# 2.net
KiCad netlist of a schematic drawn in EasyEDA Pro
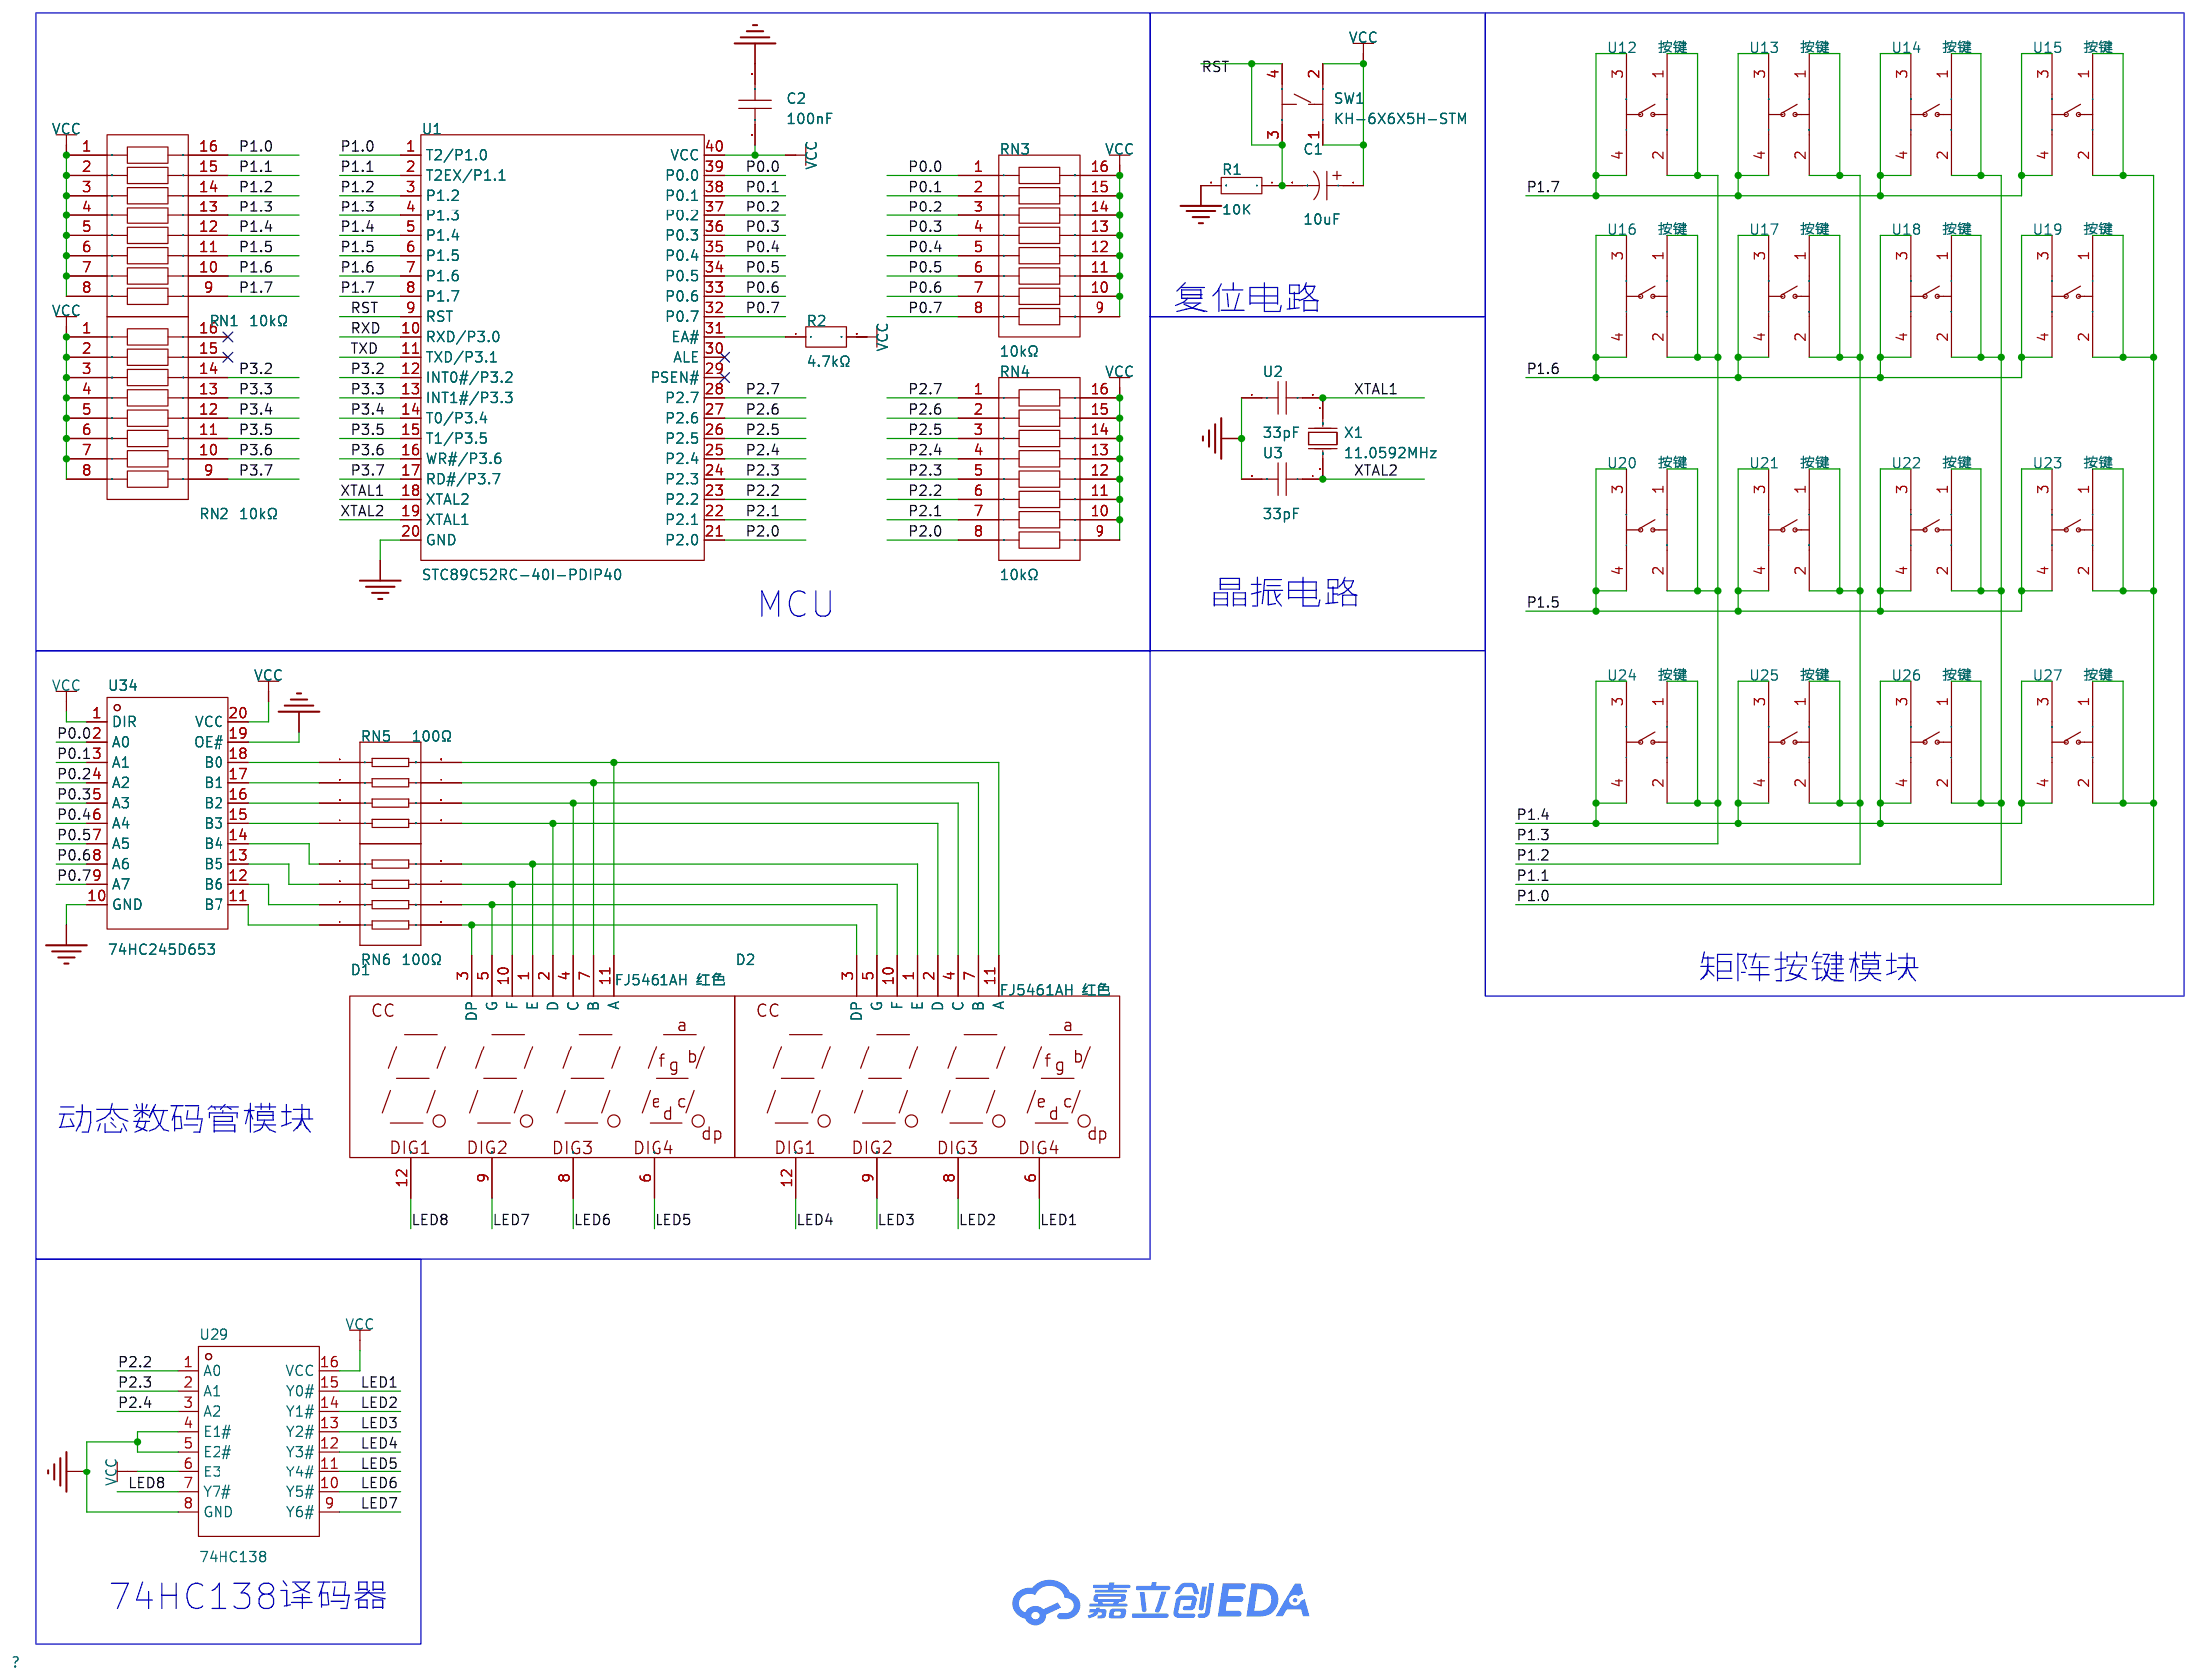
[diagram p0: schematic sheet]

(export (version "E")
  (design (tool "Eeschema 10.0.6"))
  (components
    (comp (ref "C1")
      (value "10uF")
      (footprint "easyedapro:CAP-TH_BD10.0-P5.00-D0.6-FD_1")
      (description "容值:10uF;精度:±20%;额定电压:450V;纹波电流:200mA@100kHz;等效串联电阻(ESR):9Ω@100kHz;")
      (fields (field (name "Manufacturer Part") "CV100MPA16B") (field (name "Manufacturer") "TWBOR(伯鸿)"))
      (libsource (lib "easyedapro") (part "CV100MPA16B"))
    )
    (comp (ref "C2")
      (value "100nF")
      (footprint "easyedapro:C0603")
      (description "容值:100nF;精度:±10%;额定电压:25V;温度系数:X7R;")
      (fields
        (field (name "Manufacturer Part") "0603X7R104K250NT")
        (field (name "Manufacturer") "AIDE(爱迪电容)")
      )
      (libsource (lib "easyedapro") (part "0603X7R104K250NT"))
    )
    (comp (ref "D1")
      (value "FJ5461AH 红色")
      (footprint "easyedapro:LED-SEG-TH_FJ5461AH")
      (description "数码管位数:4位;功耗:-;发光颜色:红色;LED极性:共阴极;数字/字母大小(英寸):0.56;")
      (fields (field (name "Manufacturer") "志浩"))
      (libsource (lib "easyedapro") (part "FJ5461AH red"))
    )
    (comp (ref "D2")
      (value "FJ5461AH 红色")
      (footprint "easyedapro:LED-SEG-TH_FJ5461AH")
      (description "数码管位数:4位;功耗:-;发光颜色:红色;LED极性:共阴极;数字/字母大小(英寸):0.56;")
      (fields (field (name "Manufacturer") "志浩"))
      (libsource (lib "easyedapro") (part "FJ5461AH red"))
    )
    (comp (ref "R1") (value "10K") (footprint "easyedapro:R0603") (libsource (lib "easyedapro") (part "电阻")))
    (comp (ref "R2")
      (value "4.7kΩ")
      (footprint "easyedapro:R0805")
      (description "电阻类型:厚膜电阻;阻值:4.7kΩ;精度:±1%;功率:125mW;工作电压:-;温度系数:±100ppm/°C;")
      (fields
        (field (name "Manufacturer Part") "ERJ-U06F4701V")
        (field (name "Manufacturer") "PANASONIC(松下)")
      )
      (libsource (lib "easyedapro") (part "ERJ-U06F4701V"))
    )
    (comp (ref "RN1")
      (value "10kΩ")
      (footprint "easyedapro:DIP-16_L22.0-W6.7-P2.54-LS7.6-BL")
      (description "电阻器数:8;阻值:10kΩ;精度:±2%;单个元件功率:250mW;温度系数:±100ppm/°C;")
      (fields (field (name "Manufacturer Part") "4116R-1-103LF") (field (name "Manufacturer") "BOURNS"))
      (libsource (lib "easyedapro") (part "4116R-1-103LF"))
    )
    (comp (ref "RN2")
      (value "10kΩ")
      (footprint "easyedapro:DIP-16_L22.0-W6.7-P2.54-LS7.6-BL")
      (description "电阻器数:8;阻值:10kΩ;精度:±2%;单个元件功率:250mW;温度系数:±100ppm/°C;")
      (fields (field (name "Manufacturer Part") "4116R-1-103LF") (field (name "Manufacturer") "BOURNS"))
      (libsource (lib "easyedapro") (part "4116R-1-103LF"))
    )
    (comp (ref "RN3")
      (value "10kΩ")
      (footprint "easyedapro:DIP-16_L22.0-W6.7-P2.54-LS7.6-BL")
      (description "电阻器数:8;阻值:10kΩ;精度:±2%;单个元件功率:250mW;温度系数:±100ppm/°C;")
      (fields (field (name "Manufacturer Part") "4116R-1-103LF") (field (name "Manufacturer") "BOURNS"))
      (libsource (lib "easyedapro") (part "4116R-1-103LF"))
    )
    (comp (ref "RN4")
      (value "10kΩ")
      (footprint "easyedapro:DIP-16_L22.0-W6.7-P2.54-LS7.6-BL")
      (description "电阻器数:8;阻值:10kΩ;精度:±2%;单个元件功率:250mW;温度系数:±100ppm/°C;")
      (fields (field (name "Manufacturer Part") "4116R-1-103LF") (field (name "Manufacturer") "BOURNS"))
      (libsource (lib "easyedapro") (part "4116R-1-103LF"))
    )
    (comp (ref "RN5")
      (value "100Ω")
      (footprint "easyedapro:RES-ARRAY-SMD_0402-8P-L2.0-W1.0-BL")
      (description "电阻器数:4;阻值:100Ω;精度:±5%;单个元件功率:62.5mW;温度系数:±200ppm/°C;")
      (fields
        (field (name "Manufacturer Part") "4D02WGJ0101TCE")
        (field (name "Manufacturer") "UNI-ROYAL(厚声)")
      )
      (libsource (lib "easyedapro") (part "4D02WGJ0101TCE"))
    )
    (comp (ref "RN6")
      (value "100Ω")
      (footprint "easyedapro:RES-ARRAY-SMD_0402-8P-L2.0-W1.0-BL")
      (description "电阻器数:4;阻值:100Ω;精度:±5%;单个元件功率:62.5mW;温度系数:±200ppm/°C;")
      (fields
        (field (name "Manufacturer Part") "4D02WGJ0101TCE")
        (field (name "Manufacturer") "UNI-ROYAL(厚声)")
      )
      (libsource (lib "easyedapro") (part "4D02WGJ0101TCE"))
    )
    (comp (ref "SW1")
      (value "KH-6X6X5H-STM")
      (footprint "easyedapro:SW-SMD_4P-L6.0-W6.0-P4.50-LS9.0_H5.0")
      (description "电路结构:单刀单掷;按钮形状:圆形按钮;安装方式:立贴;开关长度:6mm;开关宽度:6mm;开关高度:5mm;带支架:不带;触点电流:50mA;额定电压(DC):12V;机械寿命:8万次;")
      (fields (field (name "Manufacturer") "kinghelm(金航标)"))
      (libsource (lib "easyedapro") (part "KH-6X6X5H-STM"))
    )
    (comp (ref "U1")
      (value "STC89C52RC-40I-PDIP40")
      (footprint "easyedapro:DIP-40_L52.0-W13.7-P2.54-LS15.2-BL")
      (description "CPU内核:51系列;应用领域:-;")
      (fields (field (name "Manufacturer") "STC"))
      (libsource (lib "easyedapro") (part "STC89C52RC-40I"))
    )
    (comp (ref "U2")
      (value "33pF")
      (footprint "easyedapro:C0603")
      (description "容值:33pF;精度:±1%;额定电压:50V;温度系数:-;")
      (fields
        (field (name "Manufacturer Part") "GRM1885C1H330FA01D")
        (field (name "Manufacturer") "muRata(村田)")
      )
      (libsource (lib "easyedapro") (part "GRM1885C1H330FA01D"))
    )
    (comp (ref "U3")
      (value "33pF")
      (footprint "easyedapro:C0603")
      (description "容值:33pF;精度:±1%;额定电压:50V;温度系数:-;")
      (fields
        (field (name "Manufacturer Part") "GRM1885C1H330FA01D")
        (field (name "Manufacturer") "muRata(村田)")
      )
      (libsource (lib "easyedapro") (part "GRM1885C1H330FA01D"))
    )
    (comp (ref "U12")
      (value "按键")
      (footprint "easyedapro:SW-SMD_4P-L6.0-W6.0-P4.50-LS9.0-2")
      (libsource (lib "easyedapro") (part "SW"))
    )
    (comp (ref "U13")
      (value "按键")
      (footprint "easyedapro:SW-SMD_4P-L6.0-W6.0-P4.50-LS9.0-2")
      (libsource (lib "easyedapro") (part "SW"))
    )
    (comp (ref "U14")
      (value "按键")
      (footprint "easyedapro:SW-SMD_4P-L6.0-W6.0-P4.50-LS9.0-2")
      (libsource (lib "easyedapro") (part "SW"))
    )
    (comp (ref "U15")
      (value "按键")
      (footprint "easyedapro:SW-SMD_4P-L6.0-W6.0-P4.50-LS9.0-2")
      (libsource (lib "easyedapro") (part "SW"))
    )
    (comp (ref "U16")
      (value "按键")
      (footprint "easyedapro:SW-SMD_4P-L6.0-W6.0-P4.50-LS9.0-2")
      (libsource (lib "easyedapro") (part "SW"))
    )
    (comp (ref "U17")
      (value "按键")
      (footprint "easyedapro:SW-SMD_4P-L6.0-W6.0-P4.50-LS9.0-2")
      (libsource (lib "easyedapro") (part "SW"))
    )
    (comp (ref "U18")
      (value "按键")
      (footprint "easyedapro:SW-SMD_4P-L6.0-W6.0-P4.50-LS9.0-2")
      (libsource (lib "easyedapro") (part "SW"))
    )
    (comp (ref "U19")
      (value "按键")
      (footprint "easyedapro:SW-SMD_4P-L6.0-W6.0-P4.50-LS9.0-2")
      (libsource (lib "easyedapro") (part "SW"))
    )
    (comp (ref "U20")
      (value "按键")
      (footprint "easyedapro:SW-SMD_4P-L6.0-W6.0-P4.50-LS9.0-2")
      (libsource (lib "easyedapro") (part "SW"))
    )
    (comp (ref "U21")
      (value "按键")
      (footprint "easyedapro:SW-SMD_4P-L6.0-W6.0-P4.50-LS9.0-2")
      (libsource (lib "easyedapro") (part "SW"))
    )
    (comp (ref "U22")
      (value "按键")
      (footprint "easyedapro:SW-SMD_4P-L6.0-W6.0-P4.50-LS9.0-2")
      (libsource (lib "easyedapro") (part "SW"))
    )
    (comp (ref "U23")
      (value "按键")
      (footprint "easyedapro:SW-SMD_4P-L6.0-W6.0-P4.50-LS9.0-2")
      (libsource (lib "easyedapro") (part "SW"))
    )
    (comp (ref "U24")
      (value "按键")
      (footprint "easyedapro:SW-SMD_4P-L6.0-W6.0-P4.50-LS9.0-2")
      (libsource (lib "easyedapro") (part "SW"))
    )
    (comp (ref "U25")
      (value "按键")
      (footprint "easyedapro:SW-SMD_4P-L6.0-W6.0-P4.50-LS9.0-2")
      (libsource (lib "easyedapro") (part "SW"))
    )
    (comp (ref "U26")
      (value "按键")
      (footprint "easyedapro:SW-SMD_4P-L6.0-W6.0-P4.50-LS9.0-2")
      (libsource (lib "easyedapro") (part "SW"))
    )
    (comp (ref "U27")
      (value "按键")
      (footprint "easyedapro:SW-SMD_4P-L6.0-W6.0-P4.50-LS9.0-2")
      (libsource (lib "easyedapro") (part "SW"))
    )
    (comp (ref "U29")
      (value "74HC138")
      (footprint "easyedapro:SOIC-16_L9.9-W3.9-P1.27-LS6.0-BL")
      (description "三八译码器，74系列逻辑芯片,2.0V-6.0V供电电压。")
      (fields (field (name "Manufacturer") "FM(富满)"))
      (libsource (lib "easyedapro") (part "74HC138"))
    )
    (comp (ref "U34")
      (value "74HC245D653")
      (footprint "easyedapro:SOIC-20_L13.0-W7.6-P1.27-LS10.3-BL")
      (libsource (lib "easyedapro") (part "74HC245D653"))
    )
    (comp (ref "X1")
      (value "11.0592MHz")
      (footprint "easyedapro:HC-49US_L11.5-W4.5-P4.88")
      (description "晶振类型:直插晶振;频率:11.0592MHz;常温频差:±20ppm;负载电容:20pF;频率稳定度:±30ppm;")
      (fields
        (field (name "Manufacturer Part") "X49SD110592MSD2SC")
        (field (name "Manufacturer") "YXC(扬兴晶振)")
      )
      (libsource (lib "easyedapro") (part "X49SD110592MSD2SC"))
    )
  )
  (nets
    (net (code "1") (name "/LED1") (class "Default")
      (node (ref "D2") (pin "6") (pinfunction "DIG4_6") (pintype "input"))
      (node (ref "U29") (pin "15") (pinfunction "Y0#_15") (pintype "unspecified"))
    )
    (net (code "2") (name "/LED2") (class "Default")
      (node (ref "D2") (pin "8") (pinfunction "DIG3_8") (pintype "input"))
      (node (ref "U29") (pin "14") (pinfunction "Y1#_14") (pintype "unspecified"))
    )
    (net (code "3") (name "/LED3") (class "Default")
      (node (ref "D2") (pin "9") (pinfunction "DIG2_9") (pintype "input"))
      (node (ref "U29") (pin "13") (pinfunction "Y2#_13") (pintype "unspecified"))
    )
    (net (code "4") (name "/LED4") (class "Default")
      (node (ref "D2") (pin "12") (pinfunction "DIG1_12") (pintype "input"))
      (node (ref "U29") (pin "12") (pinfunction "Y3#_12") (pintype "unspecified"))
    )
    (net (code "5") (name "/LED5") (class "Default")
      (node (ref "D1") (pin "6") (pinfunction "DIG4_6") (pintype "input"))
      (node (ref "U29") (pin "11") (pinfunction "Y4#_11") (pintype "unspecified"))
    )
    (net (code "6") (name "/LED6") (class "Default")
      (node (ref "D1") (pin "8") (pinfunction "DIG3_8") (pintype "input"))
      (node (ref "U29") (pin "10") (pinfunction "Y5#_10") (pintype "unspecified"))
    )
    (net (code "7") (name "/LED7") (class "Default")
      (node (ref "D1") (pin "9") (pinfunction "DIG2_9") (pintype "input"))
      (node (ref "U29") (pin "9") (pinfunction "Y6#_9") (pintype "unspecified"))
    )
    (net (code "8") (name "/LED8") (class "Default")
      (node (ref "D1") (pin "12") (pinfunction "DIG1_12") (pintype "input"))
      (node (ref "U29") (pin "7") (pinfunction "Y7#_7") (pintype "unspecified"))
    )
    (net (code "9") (name "/P0.0") (class "Default")
      (node (ref "RN3") (pin "1") (pinfunction "1_1") (pintype "unspecified"))
      (node (ref "U1") (pin "39") (pinfunction "P0.0_39") (pintype "unspecified"))
      (node (ref "U34") (pin "2") (pinfunction "A0_2") (pintype "unspecified"))
    )
    (net (code "10") (name "/P0.1") (class "Default")
      (node (ref "RN3") (pin "2") (pinfunction "2_2") (pintype "unspecified"))
      (node (ref "U1") (pin "38") (pinfunction "P0.1_38") (pintype "unspecified"))
      (node (ref "U34") (pin "3") (pinfunction "A1_3") (pintype "unspecified"))
    )
    (net (code "11") (name "/P0.2") (class "Default")
      (node (ref "RN3") (pin "3") (pinfunction "3_3") (pintype "unspecified"))
      (node (ref "U1") (pin "37") (pinfunction "P0.2_37") (pintype "unspecified"))
      (node (ref "U34") (pin "4") (pinfunction "A2_4") (pintype "unspecified"))
    )
    (net (code "12") (name "/P0.3") (class "Default")
      (node (ref "RN3") (pin "4") (pinfunction "4_4") (pintype "unspecified"))
      (node (ref "U1") (pin "36") (pinfunction "P0.3_36") (pintype "unspecified"))
      (node (ref "U34") (pin "5") (pinfunction "A3_5") (pintype "unspecified"))
    )
    (net (code "13") (name "/P0.4") (class "Default")
      (node (ref "RN3") (pin "5") (pinfunction "5_5") (pintype "unspecified"))
      (node (ref "U1") (pin "35") (pinfunction "P0.4_35") (pintype "unspecified"))
      (node (ref "U34") (pin "6") (pinfunction "A4_6") (pintype "unspecified"))
    )
    (net (code "14") (name "/P0.5") (class "Default")
      (node (ref "RN3") (pin "6") (pinfunction "6_6") (pintype "unspecified"))
      (node (ref "U1") (pin "34") (pinfunction "P0.5_34") (pintype "unspecified"))
      (node (ref "U34") (pin "7") (pinfunction "A5_7") (pintype "unspecified"))
    )
    (net (code "15") (name "/P0.6") (class "Default")
      (node (ref "RN3") (pin "7") (pinfunction "7_7") (pintype "unspecified"))
      (node (ref "U1") (pin "33") (pinfunction "P0.6_33") (pintype "unspecified"))
      (node (ref "U34") (pin "8") (pinfunction "A6_8") (pintype "unspecified"))
    )
    (net (code "16") (name "/P0.7") (class "Default")
      (node (ref "RN3") (pin "8") (pinfunction "8_8") (pintype "unspecified"))
      (node (ref "U1") (pin "32") (pinfunction "P0.7_32") (pintype "unspecified"))
      (node (ref "U34") (pin "9") (pinfunction "A7_9") (pintype "unspecified"))
    )
    (net (code "17") (name "/P1.0") (class "Default")
      (node (ref "RN1") (pin "16") (pinfunction "16_16") (pintype "unspecified"))
      (node (ref "U1") (pin "1") (pinfunction "T2/P1.0_1") (pintype "unspecified"))
      (node (ref "U15") (pin "1") (pinfunction "1_1") (pintype "unspecified"))
      (node (ref "U15") (pin "2") (pinfunction "2_2") (pintype "unspecified"))
      (node (ref "U19") (pin "1") (pinfunction "1_1") (pintype "unspecified"))
      (node (ref "U19") (pin "2") (pinfunction "2_2") (pintype "unspecified"))
      (node (ref "U23") (pin "1") (pinfunction "1_1") (pintype "unspecified"))
      (node (ref "U23") (pin "2") (pinfunction "2_2") (pintype "unspecified"))
      (node (ref "U27") (pin "1") (pinfunction "1_1") (pintype "unspecified"))
      (node (ref "U27") (pin "2") (pinfunction "2_2") (pintype "unspecified"))
    )
    (net (code "18") (name "/P1.1") (class "Default")
      (node (ref "RN1") (pin "15") (pinfunction "15_15") (pintype "unspecified"))
      (node (ref "U1") (pin "2") (pinfunction "T2EX/P1.1_2") (pintype "unspecified"))
      (node (ref "U14") (pin "1") (pinfunction "1_1") (pintype "unspecified"))
      (node (ref "U14") (pin "2") (pinfunction "2_2") (pintype "unspecified"))
      (node (ref "U18") (pin "1") (pinfunction "1_1") (pintype "unspecified"))
      (node (ref "U18") (pin "2") (pinfunction "2_2") (pintype "unspecified"))
      (node (ref "U22") (pin "1") (pinfunction "1_1") (pintype "unspecified"))
      (node (ref "U22") (pin "2") (pinfunction "2_2") (pintype "unspecified"))
      (node (ref "U26") (pin "1") (pinfunction "1_1") (pintype "unspecified"))
      (node (ref "U26") (pin "2") (pinfunction "2_2") (pintype "unspecified"))
    )
    (net (code "19") (name "/P1.2") (class "Default")
      (node (ref "RN1") (pin "14") (pinfunction "14_14") (pintype "unspecified"))
      (node (ref "U1") (pin "3") (pinfunction "P1.2_3") (pintype "unspecified"))
      (node (ref "U13") (pin "1") (pinfunction "1_1") (pintype "unspecified"))
      (node (ref "U13") (pin "2") (pinfunction "2_2") (pintype "unspecified"))
      (node (ref "U17") (pin "1") (pinfunction "1_1") (pintype "unspecified"))
      (node (ref "U17") (pin "2") (pinfunction "2_2") (pintype "unspecified"))
      (node (ref "U21") (pin "1") (pinfunction "1_1") (pintype "unspecified"))
      (node (ref "U21") (pin "2") (pinfunction "2_2") (pintype "unspecified"))
      (node (ref "U25") (pin "1") (pinfunction "1_1") (pintype "unspecified"))
      (node (ref "U25") (pin "2") (pinfunction "2_2") (pintype "unspecified"))
    )
    (net (code "20") (name "/P1.3") (class "Default")
      (node (ref "RN1") (pin "13") (pinfunction "13_13") (pintype "unspecified"))
      (node (ref "U1") (pin "4") (pinfunction "P1.3_4") (pintype "unspecified"))
      (node (ref "U12") (pin "1") (pinfunction "1_1") (pintype "unspecified"))
      (node (ref "U12") (pin "2") (pinfunction "2_2") (pintype "unspecified"))
      (node (ref "U16") (pin "1") (pinfunction "1_1") (pintype "unspecified"))
      (node (ref "U16") (pin "2") (pinfunction "2_2") (pintype "unspecified"))
      (node (ref "U20") (pin "1") (pinfunction "1_1") (pintype "unspecified"))
      (node (ref "U20") (pin "2") (pinfunction "2_2") (pintype "unspecified"))
      (node (ref "U24") (pin "1") (pinfunction "1_1") (pintype "unspecified"))
      (node (ref "U24") (pin "2") (pinfunction "2_2") (pintype "unspecified"))
    )
    (net (code "21") (name "/P1.4") (class "Default")
      (node (ref "RN1") (pin "12") (pinfunction "12_12") (pintype "unspecified"))
      (node (ref "U1") (pin "5") (pinfunction "P1.4_5") (pintype "unspecified"))
      (node (ref "U24") (pin "3") (pinfunction "3_3") (pintype "unspecified"))
      (node (ref "U24") (pin "4") (pinfunction "4_4") (pintype "unspecified"))
      (node (ref "U25") (pin "3") (pinfunction "3_3") (pintype "unspecified"))
      (node (ref "U25") (pin "4") (pinfunction "4_4") (pintype "unspecified"))
      (node (ref "U26") (pin "3") (pinfunction "3_3") (pintype "unspecified"))
      (node (ref "U26") (pin "4") (pinfunction "4_4") (pintype "unspecified"))
      (node (ref "U27") (pin "3") (pinfunction "3_3") (pintype "unspecified"))
      (node (ref "U27") (pin "4") (pinfunction "4_4") (pintype "unspecified"))
    )
    (net (code "22") (name "/P1.5") (class "Default")
      (node (ref "RN1") (pin "11") (pinfunction "11_11") (pintype "unspecified"))
      (node (ref "U1") (pin "6") (pinfunction "P1.5_6") (pintype "unspecified"))
      (node (ref "U20") (pin "3") (pinfunction "3_3") (pintype "unspecified"))
      (node (ref "U20") (pin "4") (pinfunction "4_4") (pintype "unspecified"))
      (node (ref "U21") (pin "3") (pinfunction "3_3") (pintype "unspecified"))
      (node (ref "U21") (pin "4") (pinfunction "4_4") (pintype "unspecified"))
      (node (ref "U22") (pin "3") (pinfunction "3_3") (pintype "unspecified"))
      (node (ref "U22") (pin "4") (pinfunction "4_4") (pintype "unspecified"))
      (node (ref "U23") (pin "3") (pinfunction "3_3") (pintype "unspecified"))
      (node (ref "U23") (pin "4") (pinfunction "4_4") (pintype "unspecified"))
    )
    (net (code "23") (name "/P1.6") (class "Default")
      (node (ref "RN1") (pin "10") (pinfunction "10_10") (pintype "unspecified"))
      (node (ref "U1") (pin "7") (pinfunction "P1.6_7") (pintype "unspecified"))
      (node (ref "U16") (pin "3") (pinfunction "3_3") (pintype "unspecified"))
      (node (ref "U16") (pin "4") (pinfunction "4_4") (pintype "unspecified"))
      (node (ref "U17") (pin "3") (pinfunction "3_3") (pintype "unspecified"))
      (node (ref "U17") (pin "4") (pinfunction "4_4") (pintype "unspecified"))
      (node (ref "U18") (pin "3") (pinfunction "3_3") (pintype "unspecified"))
      (node (ref "U18") (pin "4") (pinfunction "4_4") (pintype "unspecified"))
      (node (ref "U19") (pin "3") (pinfunction "3_3") (pintype "unspecified"))
      (node (ref "U19") (pin "4") (pinfunction "4_4") (pintype "unspecified"))
    )
    (net (code "24") (name "/P1.7") (class "Default")
      (node (ref "RN1") (pin "9") (pinfunction "9_9") (pintype "unspecified"))
      (node (ref "U1") (pin "8") (pinfunction "P1.7_8") (pintype "unspecified"))
      (node (ref "U12") (pin "3") (pinfunction "3_3") (pintype "unspecified"))
      (node (ref "U12") (pin "4") (pinfunction "4_4") (pintype "unspecified"))
      (node (ref "U13") (pin "3") (pinfunction "3_3") (pintype "unspecified"))
      (node (ref "U13") (pin "4") (pinfunction "4_4") (pintype "unspecified"))
      (node (ref "U14") (pin "3") (pinfunction "3_3") (pintype "unspecified"))
      (node (ref "U14") (pin "4") (pinfunction "4_4") (pintype "unspecified"))
      (node (ref "U15") (pin "3") (pinfunction "3_3") (pintype "unspecified"))
      (node (ref "U15") (pin "4") (pinfunction "4_4") (pintype "unspecified"))
    )
    (net (code "25") (name "/P2.0") (class "Default")
      (node (ref "RN4") (pin "8") (pinfunction "8_8") (pintype "unspecified"))
      (node (ref "U1") (pin "21") (pinfunction "P2.0_21") (pintype "unspecified"))
    )
    (net (code "26") (name "/P2.1") (class "Default")
      (node (ref "RN4") (pin "7") (pinfunction "7_7") (pintype "unspecified"))
      (node (ref "U1") (pin "22") (pinfunction "P2.1_22") (pintype "unspecified"))
    )
    (net (code "27") (name "/P2.2") (class "Default")
      (node (ref "RN4") (pin "6") (pinfunction "6_6") (pintype "unspecified"))
      (node (ref "U1") (pin "23") (pinfunction "P2.2_23") (pintype "unspecified"))
      (node (ref "U29") (pin "1") (pinfunction "A0_1") (pintype "unspecified"))
    )
    (net (code "28") (name "/P2.3") (class "Default")
      (node (ref "RN4") (pin "5") (pinfunction "5_5") (pintype "unspecified"))
      (node (ref "U1") (pin "24") (pinfunction "P2.3_24") (pintype "unspecified"))
      (node (ref "U29") (pin "2") (pinfunction "A1_2") (pintype "unspecified"))
    )
    (net (code "29") (name "/P2.4") (class "Default")
      (node (ref "RN4") (pin "4") (pinfunction "4_4") (pintype "unspecified"))
      (node (ref "U1") (pin "25") (pinfunction "P2.4_25") (pintype "unspecified"))
      (node (ref "U29") (pin "3") (pinfunction "A2_3") (pintype "unspecified"))
    )
    (net (code "30") (name "/P2.5") (class "Default")
      (node (ref "RN4") (pin "3") (pinfunction "3_3") (pintype "unspecified"))
      (node (ref "U1") (pin "26") (pinfunction "P2.5_26") (pintype "unspecified"))
    )
    (net (code "31") (name "/P2.6") (class "Default")
      (node (ref "RN4") (pin "2") (pinfunction "2_2") (pintype "unspecified"))
      (node (ref "U1") (pin "27") (pinfunction "P2.6_27") (pintype "unspecified"))
    )
    (net (code "32") (name "/P2.7") (class "Default")
      (node (ref "RN4") (pin "1") (pinfunction "1_1") (pintype "unspecified"))
      (node (ref "U1") (pin "28") (pinfunction "P2.7_28") (pintype "unspecified"))
    )
    (net (code "33") (name "/P3.2") (class "Default")
      (node (ref "RN2") (pin "14") (pinfunction "14_14") (pintype "unspecified"))
      (node (ref "U1") (pin "12") (pinfunction "INT0#/P3.2_12") (pintype "unspecified"))
    )
    (net (code "34") (name "/P3.3") (class "Default")
      (node (ref "RN2") (pin "13") (pinfunction "13_13") (pintype "unspecified"))
      (node (ref "U1") (pin "13") (pinfunction "INT1#/P3.3_13") (pintype "unspecified"))
    )
    (net (code "35") (name "/P3.4") (class "Default")
      (node (ref "RN2") (pin "12") (pinfunction "12_12") (pintype "unspecified"))
      (node (ref "U1") (pin "14") (pinfunction "T0/P3.4_14") (pintype "unspecified"))
    )
    (net (code "36") (name "/P3.5") (class "Default")
      (node (ref "RN2") (pin "11") (pinfunction "11_11") (pintype "unspecified"))
      (node (ref "U1") (pin "15") (pinfunction "T1/P3.5_15") (pintype "unspecified"))
    )
    (net (code "37") (name "/P3.6") (class "Default")
      (node (ref "RN2") (pin "10") (pinfunction "10_10") (pintype "unspecified"))
      (node (ref "U1") (pin "16") (pinfunction "WR#/P3.6_16") (pintype "unspecified"))
    )
    (net (code "38") (name "/P3.7") (class "Default")
      (node (ref "RN2") (pin "9") (pinfunction "9_9") (pintype "unspecified"))
      (node (ref "U1") (pin "17") (pinfunction "RD#/P3.7_17") (pintype "unspecified"))
    )
    (net (code "39") (name "/RST") (class "Default")
      (node (ref "C1") (pin "2") (pinfunction "2_2") (pintype "input"))
      (node (ref "R1") (pin "1") (pinfunction "1_1") (pintype "input"))
      (node (ref "SW1") (pin "3") (pinfunction "3_3") (pintype "unspecified"))
      (node (ref "SW1") (pin "4") (pinfunction "4_4") (pintype "unspecified"))
      (node (ref "U1") (pin "9") (pinfunction "RST_9") (pintype "unspecified"))
    )
    (net (code "40") (name "/RXD") (class "Default")
      (node (ref "U1") (pin "10") (pinfunction "RXD/P3.0_10") (pintype "unspecified"))
    )
    (net (code "41") (name "/TXD") (class "Default")
      (node (ref "U1") (pin "11") (pinfunction "TXD/P3.1_11") (pintype "unspecified"))
    )
    (net (code "42") (name "/XTAL1") (class "Default")
      (node (ref "U1") (pin "18") (pinfunction "XTAL2_18") (pintype "unspecified"))
      (node (ref "U2") (pin "2") (pinfunction "2_2") (pintype "unspecified"))
      (node (ref "X1") (pin "1") (pinfunction "OSC1_1") (pintype "input"))
    )
    (net (code "43") (name "/XTAL2") (class "Default")
      (node (ref "U1") (pin "19") (pinfunction "XTAL1_19") (pintype "unspecified"))
      (node (ref "U3") (pin "1") (pinfunction "1_1") (pintype "unspecified"))
      (node (ref "X1") (pin "2") (pinfunction "OSC2_2") (pintype "input"))
    )
    (net (code "44") (name "GND") (class "Default")
      (node (ref "C2") (pin "2") (pinfunction "2_2") (pintype "unspecified"))
      (node (ref "R1") (pin "2") (pinfunction "2_2") (pintype "input"))
      (node (ref "U1") (pin "20") (pinfunction "GND_20") (pintype "unspecified"))
      (node (ref "U2") (pin "1") (pinfunction "1_1") (pintype "unspecified"))
      (node (ref "U29") (pin "4") (pinfunction "E1#_4") (pintype "unspecified"))
      (node (ref "U29") (pin "5") (pinfunction "E2#_5") (pintype "unspecified"))
      (node (ref "U29") (pin "8") (pinfunction "GND_8") (pintype "unspecified"))
      (node (ref "U3") (pin "2") (pinfunction "2_2") (pintype "unspecified"))
      (node (ref "U34") (pin "10") (pinfunction "GND_10") (pintype "unspecified"))
      (node (ref "U34") (pin "19") (pinfunction "OE#_19") (pintype "unspecified"))
    )
    (net (code "45") (name "Net-(D1-A)") (class "Default")
      (node (ref "D1") (pin "11") (pinfunction "A_11") (pintype "input"))
      (node (ref "D2") (pin "11") (pinfunction "A_11") (pintype "input"))
      (node (ref "RN5") (pin "8") (pinfunction "8_8") (pintype "input"))
    )
    (net (code "46") (name "Net-(D1-B)") (class "Default")
      (node (ref "D1") (pin "7") (pinfunction "B_7") (pintype "input"))
      (node (ref "D2") (pin "7") (pinfunction "B_7") (pintype "input"))
      (node (ref "RN5") (pin "7") (pinfunction "7_7") (pintype "input"))
    )
    (net (code "47") (name "Net-(D1-C)") (class "Default")
      (node (ref "D1") (pin "4") (pinfunction "C_4") (pintype "input"))
      (node (ref "D2") (pin "4") (pinfunction "C_4") (pintype "input"))
      (node (ref "RN5") (pin "6") (pinfunction "6_6") (pintype "input"))
    )
    (net (code "48") (name "Net-(D1-D)") (class "Default")
      (node (ref "D1") (pin "2") (pinfunction "D_2") (pintype "input"))
      (node (ref "D2") (pin "2") (pinfunction "D_2") (pintype "input"))
      (node (ref "RN5") (pin "5") (pinfunction "5_5") (pintype "input"))
    )
    (net (code "49") (name "Net-(D1-DP)") (class "Default")
      (node (ref "D1") (pin "3") (pinfunction "DP_3") (pintype "input"))
      (node (ref "D2") (pin "3") (pinfunction "DP_3") (pintype "input"))
      (node (ref "RN6") (pin "5") (pinfunction "5_5") (pintype "input"))
    )
    (net (code "50") (name "Net-(D1-E)") (class "Default")
      (node (ref "D1") (pin "1") (pinfunction "E_1") (pintype "input"))
      (node (ref "D2") (pin "1") (pinfunction "E_1") (pintype "input"))
      (node (ref "RN6") (pin "8") (pinfunction "8_8") (pintype "input"))
    )
    (net (code "51") (name "Net-(D1-F)") (class "Default")
      (node (ref "D1") (pin "10") (pinfunction "F_10") (pintype "input"))
      (node (ref "D2") (pin "10") (pinfunction "F_10") (pintype "input"))
      (node (ref "RN6") (pin "7") (pinfunction "7_7") (pintype "input"))
    )
    (net (code "52") (name "Net-(D1-G)") (class "Default")
      (node (ref "D1") (pin "5") (pinfunction "G_5") (pintype "input"))
      (node (ref "D2") (pin "5") (pinfunction "G_5") (pintype "input"))
      (node (ref "RN6") (pin "6") (pinfunction "6_6") (pintype "input"))
    )
    (net (code "53") (name "Net-(U1-EA#)") (class "Default")
      (node (ref "R2") (pin "1") (pinfunction "1_1") (pintype "unspecified"))
      (node (ref "U1") (pin "31") (pinfunction "EA#_31") (pintype "unspecified"))
    )
    (net (code "54") (name "Net-(U34-B0)") (class "Default")
      (node (ref "RN5") (pin "1") (pinfunction "1_1") (pintype "input"))
      (node (ref "U34") (pin "18") (pinfunction "B0_18") (pintype "unspecified"))
    )
    (net (code "55") (name "Net-(U34-B1)") (class "Default")
      (node (ref "RN5") (pin "2") (pinfunction "2_2") (pintype "input"))
      (node (ref "U34") (pin "17") (pinfunction "B1_17") (pintype "unspecified"))
    )
    (net (code "56") (name "Net-(U34-B2)") (class "Default")
      (node (ref "RN5") (pin "3") (pinfunction "3_3") (pintype "input"))
      (node (ref "U34") (pin "16") (pinfunction "B2_16") (pintype "unspecified"))
    )
    (net (code "57") (name "Net-(U34-B3)") (class "Default")
      (node (ref "RN5") (pin "4") (pinfunction "4_4") (pintype "input"))
      (node (ref "U34") (pin "15") (pinfunction "B3_15") (pintype "unspecified"))
    )
    (net (code "58") (name "Net-(U34-B4)") (class "Default")
      (node (ref "RN6") (pin "1") (pinfunction "1_1") (pintype "input"))
      (node (ref "U34") (pin "14") (pinfunction "B4_14") (pintype "unspecified"))
    )
    (net (code "59") (name "Net-(U34-B5)") (class "Default")
      (node (ref "RN6") (pin "2") (pinfunction "2_2") (pintype "input"))
      (node (ref "U34") (pin "13") (pinfunction "B5_13") (pintype "unspecified"))
    )
    (net (code "60") (name "Net-(U34-B6)") (class "Default")
      (node (ref "RN6") (pin "3") (pinfunction "3_3") (pintype "input"))
      (node (ref "U34") (pin "12") (pinfunction "B6_12") (pintype "unspecified"))
    )
    (net (code "61") (name "Net-(U34-B7)") (class "Default")
      (node (ref "RN6") (pin "4") (pinfunction "4_4") (pintype "input"))
      (node (ref "U34") (pin "11") (pinfunction "B7_11") (pintype "unspecified"))
    )
    (net (code "62") (name "VCC") (class "Default")
      (node (ref "C1") (pin "1") (pinfunction "1_1") (pintype "input"))
      (node (ref "C2") (pin "1") (pinfunction "1_1") (pintype "unspecified"))
      (node (ref "R2") (pin "2") (pinfunction "2_2") (pintype "unspecified"))
      (node (ref "RN1") (pin "1") (pinfunction "1_1") (pintype "unspecified"))
      (node (ref "RN1") (pin "2") (pinfunction "2_2") (pintype "unspecified"))
      (node (ref "RN1") (pin "3") (pinfunction "3_3") (pintype "unspecified"))
      (node (ref "RN1") (pin "4") (pinfunction "4_4") (pintype "unspecified"))
      (node (ref "RN1") (pin "5") (pinfunction "5_5") (pintype "unspecified"))
      (node (ref "RN1") (pin "6") (pinfunction "6_6") (pintype "unspecified"))
      (node (ref "RN1") (pin "7") (pinfunction "7_7") (pintype "unspecified"))
      (node (ref "RN1") (pin "8") (pinfunction "8_8") (pintype "unspecified"))
      (node (ref "RN2") (pin "1") (pinfunction "1_1") (pintype "unspecified"))
      (node (ref "RN2") (pin "2") (pinfunction "2_2") (pintype "unspecified"))
      (node (ref "RN2") (pin "3") (pinfunction "3_3") (pintype "unspecified"))
      (node (ref "RN2") (pin "4") (pinfunction "4_4") (pintype "unspecified"))
      (node (ref "RN2") (pin "5") (pinfunction "5_5") (pintype "unspecified"))
      (node (ref "RN2") (pin "6") (pinfunction "6_6") (pintype "unspecified"))
      (node (ref "RN2") (pin "7") (pinfunction "7_7") (pintype "unspecified"))
      (node (ref "RN2") (pin "8") (pinfunction "8_8") (pintype "unspecified"))
      (node (ref "RN3") (pin "10") (pinfunction "10_10") (pintype "unspecified"))
      (node (ref "RN3") (pin "11") (pinfunction "11_11") (pintype "unspecified"))
      (node (ref "RN3") (pin "12") (pinfunction "12_12") (pintype "unspecified"))
      (node (ref "RN3") (pin "13") (pinfunction "13_13") (pintype "unspecified"))
      (node (ref "RN3") (pin "14") (pinfunction "14_14") (pintype "unspecified"))
      (node (ref "RN3") (pin "15") (pinfunction "15_15") (pintype "unspecified"))
      (node (ref "RN3") (pin "16") (pinfunction "16_16") (pintype "unspecified"))
      (node (ref "RN3") (pin "9") (pinfunction "9_9") (pintype "unspecified"))
      (node (ref "RN4") (pin "10") (pinfunction "10_10") (pintype "unspecified"))
      (node (ref "RN4") (pin "11") (pinfunction "11_11") (pintype "unspecified"))
      (node (ref "RN4") (pin "12") (pinfunction "12_12") (pintype "unspecified"))
      (node (ref "RN4") (pin "13") (pinfunction "13_13") (pintype "unspecified"))
      (node (ref "RN4") (pin "14") (pinfunction "14_14") (pintype "unspecified"))
      (node (ref "RN4") (pin "15") (pinfunction "15_15") (pintype "unspecified"))
      (node (ref "RN4") (pin "16") (pinfunction "16_16") (pintype "unspecified"))
      (node (ref "RN4") (pin "9") (pinfunction "9_9") (pintype "unspecified"))
      (node (ref "SW1") (pin "1") (pinfunction "1_1") (pintype "unspecified"))
      (node (ref "SW1") (pin "2") (pinfunction "2_2") (pintype "unspecified"))
      (node (ref "U1") (pin "40") (pinfunction "VCC_40") (pintype "unspecified"))
      (node (ref "U29") (pin "16") (pinfunction "VCC_16") (pintype "unspecified"))
      (node (ref "U29") (pin "6") (pinfunction "E3_6") (pintype "unspecified"))
      (node (ref "U34") (pin "1") (pinfunction "DIR_1") (pintype "unspecified"))
      (node (ref "U34") (pin "20") (pinfunction "VCC_20") (pintype "unspecified"))
    )
    (net (code "63") (name "unconnected-(RN2-Pad15)") (class "Default")
      (node (ref "RN2") (pin "15") (pinfunction "15_15") (pintype "unspecified+no_connect"))
    )
    (net (code "64") (name "unconnected-(RN2-Pad16)") (class "Default")
      (node (ref "RN2") (pin "16") (pinfunction "16_16") (pintype "unspecified+no_connect"))
    )
    (net (code "65") (name "unconnected-(U1-ALE-Pad30)") (class "Default")
      (node (ref "U1") (pin "30") (pinfunction "ALE_30") (pintype "unspecified+no_connect"))
    )
    (net (code "66") (name "unconnected-(U1-PSEN#-Pad29)") (class "Default")
      (node (ref "U1") (pin "29") (pinfunction "PSEN#_29") (pintype "unspecified+no_connect"))
    )
  )
)
